# 01_MCU.net
KiCad netlist of a schematic drawn in Altium Designer
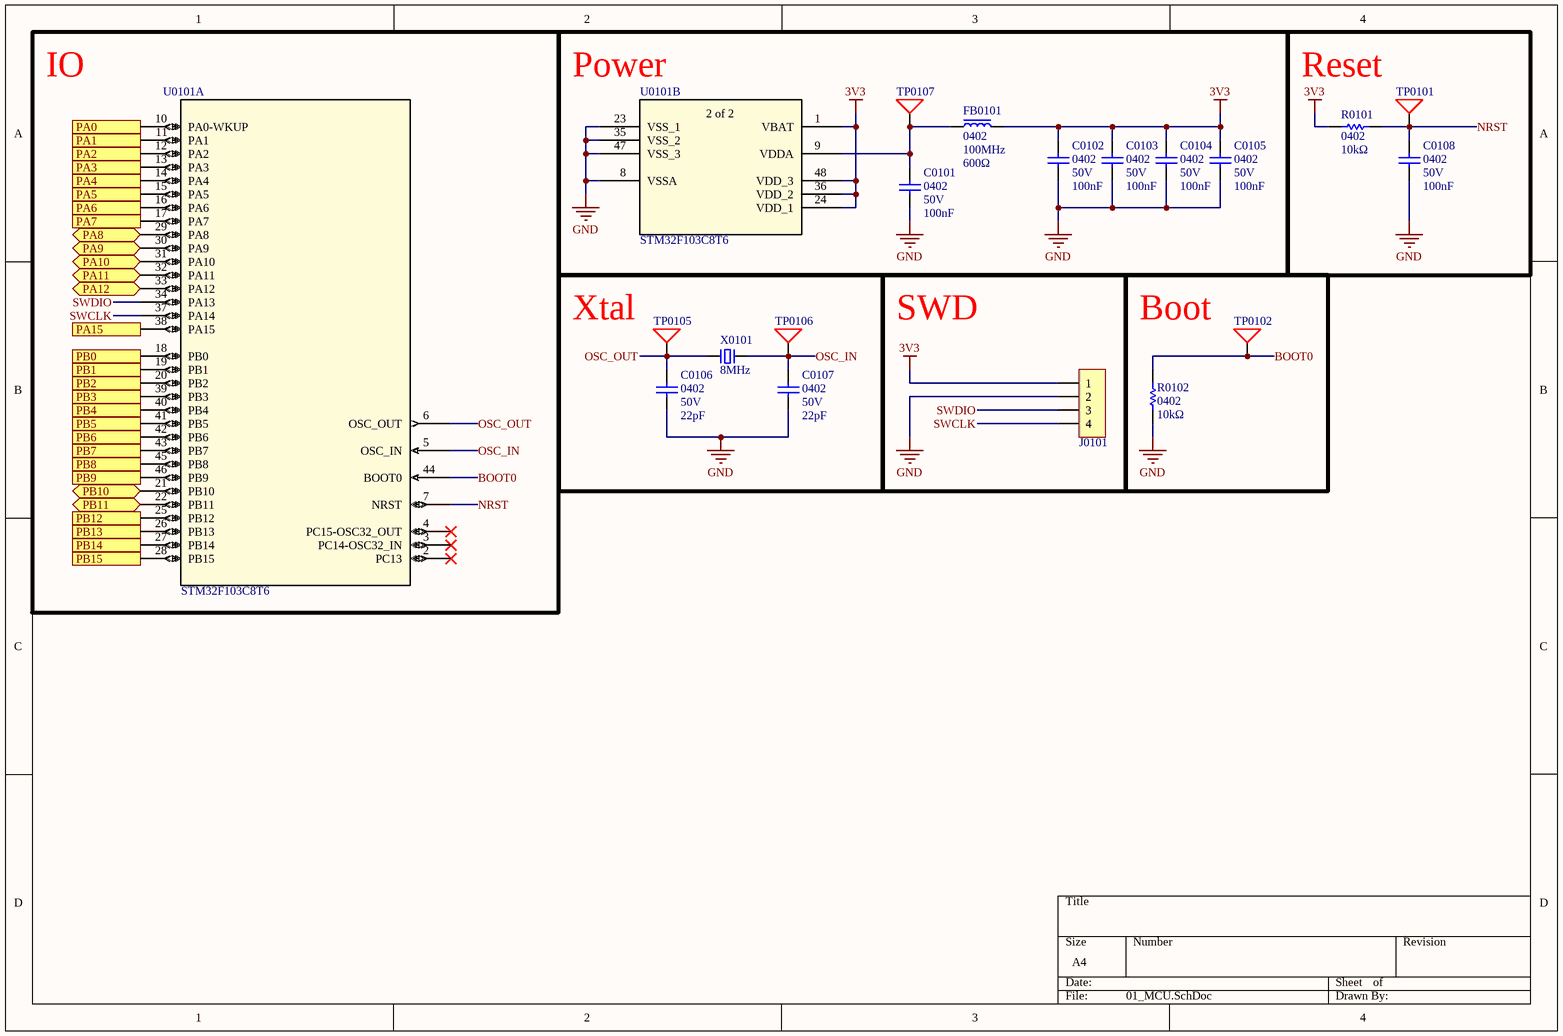
[diagram p0: 01_MCU.SchDoc]

(export (version "E")
  (design (tool "Eeschema 10.0.6"))
  (components
    (comp (ref "C0101")
      (value "Cap")
      (footprint "C0402")
      (fields (field (name "SIZE") "0402") (field (name "VOLT") "50V") (field (name "CAP") "100nF"))
      (libsource (lib "LCR") (part "Cap"))
    )
    (comp (ref "C0102")
      (value "Cap")
      (footprint "C0402")
      (fields (field (name "SIZE") "0402") (field (name "VOLT") "50V") (field (name "CAP") "100nF"))
      (libsource (lib "LCR") (part "Cap"))
    )
    (comp (ref "C0103")
      (value "Cap")
      (footprint "C0402")
      (fields (field (name "SIZE") "0402") (field (name "VOLT") "50V") (field (name "CAP") "100nF"))
      (libsource (lib "LCR") (part "Cap"))
    )
    (comp (ref "C0104")
      (value "Cap")
      (footprint "C0402")
      (fields (field (name "SIZE") "0402") (field (name "VOLT") "50V") (field (name "CAP") "100nF"))
      (libsource (lib "LCR") (part "Cap"))
    )
    (comp (ref "C0105")
      (value "Cap")
      (footprint "C0402")
      (fields (field (name "SIZE") "0402") (field (name "VOLT") "50V") (field (name "CAP") "100nF"))
      (libsource (lib "LCR") (part "Cap"))
    )
    (comp (ref "C0106")
      (value "Cap")
      (footprint "C0402")
      (fields (field (name "SIZE") "0402") (field (name "VOLT") "50V") (field (name "CAP") "22pF"))
      (libsource (lib "LCR") (part "Cap"))
    )
    (comp (ref "C0107")
      (value "Cap")
      (footprint "C0402")
      (fields (field (name "SIZE") "0402") (field (name "VOLT") "50V") (field (name "CAP") "22pF"))
      (libsource (lib "LCR") (part "Cap"))
    )
    (comp (ref "C0108")
      (value "Cap")
      (footprint "C0402")
      (fields (field (name "SIZE") "0402") (field (name "VOLT") "50V") (field (name "CAP") "100nF"))
      (libsource (lib "LCR") (part "Cap"))
    )
    (comp (ref "FB0101")
      (value "FB")
      (footprint "FB 0402")
      (description "磁珠")
      (fields (field (name "SIZE") "0402") (field (name "FREQ") "100MHz") (field (name "RES") "600Ω"))
      (libsource (lib "LCR") (part "FB"))
    )
    (comp (ref "J0101")
      (value "HDR-1X4")
      (footprint "XH2.54-4P")
      (description "4P接插件")
      (fields (field (name "版权归属") "源创客"))
      (libsource (lib "Interface") (part "Header 4P"))
    )
    (comp (ref "R0101")
      (value "RES")
      (footprint "R0402")
      (description "电阻")
      (fields (field (name "SIZE") "0402") (field (name "RES") "10kΩ"))
      (libsource (lib "LCR") (part "RES"))
    )
    (comp (ref "R0102")
      (value "RES")
      (footprint "R0402")
      (description "电阻")
      (fields (field (name "SIZE") "0402") (field (name "RES") "10kΩ"))
      (libsource (lib "LCR") (part "RES"))
    )
    (comp (ref "TP0101")
      (value "Test Point")
      (footprint "Test Point")
      (libsource (lib "Interface") (part "Test Point"))
    )
    (comp (ref "TP0102")
      (value "Test Point")
      (footprint "Test Point")
      (libsource (lib "Interface") (part "Test Point"))
    )
    (comp (ref "TP0105")
      (value "Test Point")
      (footprint "Test Point")
      (libsource (lib "Interface") (part "Test Point"))
    )
    (comp (ref "TP0106")
      (value "Test Point")
      (footprint "Test Point")
      (libsource (lib "Interface") (part "Test Point"))
    )
    (comp (ref "TP0107")
      (value "Test Point")
      (footprint "Test Point")
      (libsource (lib "Interface") (part "Test Point"))
    )
    (comp (ref "U0101")
      (value "STM32F103C8T6")
      (footprint "LQFP48_STM-M")
      (description "No Description Available")
      (libsource (lib "MCU") (part "STM32F103C8T6"))
    )
    (comp (ref "X0101")
      (value "8MHz")
      (footprint "XTAL-2P 5032")
      (description "2脚晶振")
      (fields (field (name "版权归属") "源创客"))
      (libsource (lib "LCR") (part "XTAL-2"))
    )
  )
  (nets
    (net (code "1") (name "/BOOT0") (class "Default")
      (node (ref "R0102") (pin "2") (pinfunction "2_2") (pintype "passive"))
      (node (ref "TP0102") (pin "1") (pinfunction "1_1") (pintype "passive"))
      (node (ref "U0101") (pin "44") (pinfunction "BOOT0_44") (pintype "input"))
    )
    (net (code "2") (name "/NRST") (class "Default")
      (node (ref "C0108") (pin "2") (pinfunction "2_2") (pintype "passive"))
      (node (ref "R0101") (pin "2") (pinfunction "2_2") (pintype "passive"))
      (node (ref "TP0101") (pin "1") (pinfunction "1_1") (pintype "passive"))
      (node (ref "U0101") (pin "7") (pinfunction "NRST_7") (pintype "bidirectional"))
    )
    (net (code "3") (name "/OSC_IN") (class "Default")
      (node (ref "C0107") (pin "2") (pinfunction "2_2") (pintype "passive"))
      (node (ref "TP0106") (pin "1") (pinfunction "1_1") (pintype "passive"))
      (node (ref "U0101") (pin "5") (pinfunction "OSC_IN_5") (pintype "input"))
      (node (ref "X0101") (pin "2") (pinfunction "2_2") (pintype "passive"))
    )
    (net (code "4") (name "/OSC_OUT") (class "Default")
      (node (ref "C0106") (pin "2") (pinfunction "2_2") (pintype "passive"))
      (node (ref "TP0105") (pin "1") (pinfunction "1_1") (pintype "passive"))
      (node (ref "U0101") (pin "6") (pinfunction "OSC_OUT_6") (pintype "output"))
      (node (ref "X0101") (pin "1") (pinfunction "1_1") (pintype "passive"))
    )
    (net (code "5") (name "/PA0") (class "Default")
      (node (ref "U0101") (pin "10") (pinfunction "PA0-WKUP_10") (pintype "bidirectional"))
    )
    (net (code "6") (name "/PA1") (class "Default")
      (node (ref "U0101") (pin "11") (pinfunction "PA1_11") (pintype "bidirectional"))
    )
    (net (code "7") (name "/PA2") (class "Default")
      (node (ref "U0101") (pin "12") (pinfunction "PA2_12") (pintype "bidirectional"))
    )
    (net (code "8") (name "/PA3") (class "Default")
      (node (ref "U0101") (pin "13") (pinfunction "PA3_13") (pintype "bidirectional"))
    )
    (net (code "9") (name "/PA4") (class "Default")
      (node (ref "U0101") (pin "14") (pinfunction "PA4_14") (pintype "bidirectional"))
    )
    (net (code "10") (name "/PA5") (class "Default")
      (node (ref "U0101") (pin "15") (pinfunction "PA5_15") (pintype "bidirectional"))
    )
    (net (code "11") (name "/PA6") (class "Default")
      (node (ref "U0101") (pin "16") (pinfunction "PA6_16") (pintype "bidirectional"))
    )
    (net (code "12") (name "/PA7") (class "Default")
      (node (ref "U0101") (pin "17") (pinfunction "PA7_17") (pintype "bidirectional"))
    )
    (net (code "13") (name "/PA8") (class "Default")
      (node (ref "U0101") (pin "29") (pinfunction "PA8_29") (pintype "bidirectional"))
    )
    (net (code "14") (name "/PA9") (class "Default")
      (node (ref "U0101") (pin "30") (pinfunction "PA9_30") (pintype "bidirectional"))
    )
    (net (code "15") (name "/PA10") (class "Default")
      (node (ref "U0101") (pin "31") (pinfunction "PA10_31") (pintype "bidirectional"))
    )
    (net (code "16") (name "/PA11") (class "Default")
      (node (ref "U0101") (pin "32") (pinfunction "PA11_32") (pintype "bidirectional"))
    )
    (net (code "17") (name "/PA12") (class "Default")
      (node (ref "U0101") (pin "33") (pinfunction "PA12_33") (pintype "bidirectional"))
    )
    (net (code "18") (name "/PA15") (class "Default")
      (node (ref "U0101") (pin "38") (pinfunction "PA15_38") (pintype "bidirectional"))
    )
    (net (code "19") (name "/PB0") (class "Default")
      (node (ref "U0101") (pin "18") (pinfunction "PB0_18") (pintype "bidirectional"))
    )
    (net (code "20") (name "/PB1") (class "Default")
      (node (ref "U0101") (pin "19") (pinfunction "PB1_19") (pintype "bidirectional"))
    )
    (net (code "21") (name "/PB2") (class "Default")
      (node (ref "U0101") (pin "20") (pinfunction "PB2_20") (pintype "bidirectional"))
    )
    (net (code "22") (name "/PB3") (class "Default")
      (node (ref "U0101") (pin "39") (pinfunction "PB3_39") (pintype "bidirectional"))
    )
    (net (code "23") (name "/PB4") (class "Default")
      (node (ref "U0101") (pin "40") (pinfunction "PB4_40") (pintype "bidirectional"))
    )
    (net (code "24") (name "/PB5") (class "Default")
      (node (ref "U0101") (pin "41") (pinfunction "PB5_41") (pintype "bidirectional"))
    )
    (net (code "25") (name "/PB6") (class "Default")
      (node (ref "U0101") (pin "42") (pinfunction "PB6_42") (pintype "bidirectional"))
    )
    (net (code "26") (name "/PB7") (class "Default")
      (node (ref "U0101") (pin "43") (pinfunction "PB7_43") (pintype "bidirectional"))
    )
    (net (code "27") (name "/PB8") (class "Default")
      (node (ref "U0101") (pin "45") (pinfunction "PB8_45") (pintype "bidirectional"))
    )
    (net (code "28") (name "/PB9") (class "Default")
      (node (ref "U0101") (pin "46") (pinfunction "PB9_46") (pintype "bidirectional"))
    )
    (net (code "29") (name "/PB10") (class "Default")
      (node (ref "U0101") (pin "21") (pinfunction "PB10_21") (pintype "bidirectional"))
    )
    (net (code "30") (name "/PB11") (class "Default")
      (node (ref "U0101") (pin "22") (pinfunction "PB11_22") (pintype "bidirectional"))
    )
    (net (code "31") (name "/PB12") (class "Default")
      (node (ref "U0101") (pin "25") (pinfunction "PB12_25") (pintype "bidirectional"))
    )
    (net (code "32") (name "/PB13") (class "Default")
      (node (ref "U0101") (pin "26") (pinfunction "PB13_26") (pintype "bidirectional"))
    )
    (net (code "33") (name "/PB14") (class "Default")
      (node (ref "U0101") (pin "27") (pinfunction "PB14_27") (pintype "bidirectional"))
    )
    (net (code "34") (name "/PB15") (class "Default")
      (node (ref "U0101") (pin "28") (pinfunction "PB15_28") (pintype "bidirectional"))
    )
    (net (code "35") (name "/SWCLK") (class "Default")
      (node (ref "J0101") (pin "4") (pinfunction "4_4") (pintype "passive"))
      (node (ref "U0101") (pin "37") (pinfunction "PA14_37") (pintype "bidirectional"))
    )
    (net (code "36") (name "/SWDIO") (class "Default")
      (node (ref "J0101") (pin "3") (pinfunction "3_3") (pintype "passive"))
      (node (ref "U0101") (pin "34") (pinfunction "PA13_34") (pintype "bidirectional"))
    )
    (net (code "37") (name "3V3") (class "Default")
      (node (ref "C0102") (pin "2") (pinfunction "2_2") (pintype "passive"))
      (node (ref "C0103") (pin "2") (pinfunction "2_2") (pintype "passive"))
      (node (ref "C0104") (pin "2") (pinfunction "2_2") (pintype "passive"))
      (node (ref "C0105") (pin "2") (pinfunction "2_2") (pintype "passive"))
      (node (ref "FB0101") (pin "2") (pinfunction "2_2") (pintype "passive"))
      (node (ref "J0101") (pin "1") (pinfunction "1_1") (pintype "passive"))
      (node (ref "R0101") (pin "1") (pinfunction "1_1") (pintype "passive"))
      (node (ref "U0101") (pin "1") (pinfunction "VBAT_1") (pintype "power_in"))
      (node (ref "U0101") (pin "24") (pinfunction "VDD_1_24") (pintype "power_in"))
      (node (ref "U0101") (pin "36") (pinfunction "VDD_2_36") (pintype "power_in"))
      (node (ref "U0101") (pin "48") (pinfunction "VDD_3_48") (pintype "power_in"))
    )
    (net (code "38") (name "GND") (class "Default")
      (node (ref "C0101") (pin "1") (pinfunction "1_1") (pintype "passive"))
      (node (ref "C0102") (pin "1") (pinfunction "1_1") (pintype "passive"))
      (node (ref "C0103") (pin "1") (pinfunction "1_1") (pintype "passive"))
      (node (ref "C0104") (pin "1") (pinfunction "1_1") (pintype "passive"))
      (node (ref "C0105") (pin "1") (pinfunction "1_1") (pintype "passive"))
      (node (ref "C0106") (pin "1") (pinfunction "1_1") (pintype "passive"))
      (node (ref "C0107") (pin "1") (pinfunction "1_1") (pintype "passive"))
      (node (ref "C0108") (pin "1") (pinfunction "1_1") (pintype "passive"))
      (node (ref "J0101") (pin "2") (pinfunction "2_2") (pintype "passive"))
      (node (ref "R0102") (pin "1") (pinfunction "1_1") (pintype "passive"))
      (node (ref "U0101") (pin "23") (pinfunction "VSS_1_23") (pintype "power_in"))
      (node (ref "U0101") (pin "35") (pinfunction "VSS_2_35") (pintype "power_in"))
      (node (ref "U0101") (pin "47") (pinfunction "VSS_3_47") (pintype "power_in"))
      (node (ref "U0101") (pin "8") (pinfunction "VSSA_8") (pintype "power_in"))
    )
    (net (code "39") (name "Net-(U0101B-VDDA)") (class "Default")
      (node (ref "C0101") (pin "2") (pinfunction "2_2") (pintype "passive"))
      (node (ref "FB0101") (pin "1") (pinfunction "1_1") (pintype "passive"))
      (node (ref "TP0107") (pin "1") (pinfunction "1_1") (pintype "passive"))
      (node (ref "U0101") (pin "9") (pinfunction "VDDA_9") (pintype "power_in"))
    )
    (net (code "40") (name "unconnected-(U0101A-PC13-Pad2)") (class "Default")
      (node (ref "U0101") (pin "2") (pinfunction "PC13_2") (pintype "bidirectional+no_connect"))
    )
    (net (code "41") (name "unconnected-(U0101A-PC14-OSC32_IN-Pad3)") (class "Default")
      (node (ref "U0101") (pin "3") (pinfunction "PC14-OSC32_IN_3") (pintype "bidirectional+no_connect"))
    )
    (net (code "42") (name "unconnected-(U0101A-PC15-OSC32_OUT-Pad4)") (class "Default")
      (node (ref "U0101") (pin "4") (pinfunction "PC15-OSC32_OUT_4") (pintype "bidirectional+no_connect"))
    )
  )
)
